# NO2_Output_Processing.net
KiCad netlist of a schematic drawn in Altium Designer
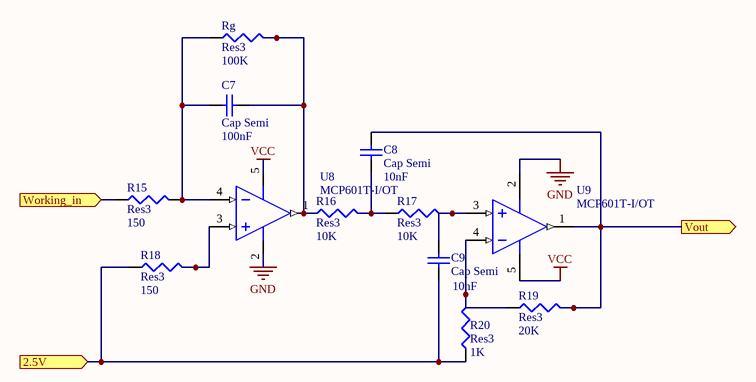
[diagram p0: NO2_Output_Processing.SchDoc]

(export (version "E")
  (design (tool "Eeschema 10.0.6"))
  (components
    (comp (ref "C7")
      (value "Cap Semi")
      (footprint "C1206")
      (description "Capacitor (Semiconductor SIM Model)")
      (fields (field (name "ALTIUM_VALUE") "100nF") (field (name "PUBLISHER") "Altium Limited"))
      (libsource (lib "Miscellaneous Devices") (part "Cap Semi"))
    )
    (comp (ref "C8")
      (value "Cap Semi")
      (footprint "C1206")
      (description "Capacitor (Semiconductor SIM Model)")
      (fields (field (name "ALTIUM_VALUE") "10nF") (field (name "PUBLISHER") "Altium Limited"))
      (libsource (lib "Miscellaneous Devices") (part "Cap Semi"))
    )
    (comp (ref "C9")
      (value "Cap Semi")
      (footprint "C1206")
      (description "Capacitor (Semiconductor SIM Model)")
      (fields (field (name "ALTIUM_VALUE") "10nF") (field (name "PUBLISHER") "Altium Limited"))
      (libsource (lib "Miscellaneous Devices") (part "Cap Semi"))
    )
    (comp (ref "R15")
      (value "Res3")
      (footprint "J1-0603")
      (description "Resistor")
      (fields (field (name "ALTIUM_VALUE") "150") (field (name "PUBLISHER") "Altium Limited"))
      (libsource (lib "Miscellaneous Devices") (part "Res3"))
    )
    (comp (ref "R16")
      (value "Res3")
      (footprint "J1-0603")
      (description "Resistor")
      (fields (field (name "ALTIUM_VALUE") "10K") (field (name "PUBLISHER") "Altium Limited"))
      (libsource (lib "Miscellaneous Devices") (part "Res3"))
    )
    (comp (ref "R17")
      (value "Res3")
      (footprint "J1-0603")
      (description "Resistor")
      (fields (field (name "ALTIUM_VALUE") "10K") (field (name "PUBLISHER") "Altium Limited"))
      (libsource (lib "Miscellaneous Devices") (part "Res3"))
    )
    (comp (ref "R18")
      (value "Res3")
      (footprint "J1-0603")
      (description "Resistor")
      (fields (field (name "ALTIUM_VALUE") "150") (field (name "PUBLISHER") "Altium Limited"))
      (libsource (lib "Miscellaneous Devices") (part "Res3"))
    )
    (comp (ref "R19")
      (value "Res3")
      (footprint "J1-0603")
      (description "Resistor")
      (fields (field (name "ALTIUM_VALUE") "20K") (field (name "PUBLISHER") "Altium Limited"))
      (libsource (lib "Miscellaneous Devices") (part "Res3"))
    )
    (comp (ref "R20")
      (value "Res3")
      (footprint "J1-0603")
      (description "Resistor")
      (fields (field (name "ALTIUM_VALUE") "1K") (field (name "PUBLISHER") "Altium Limited"))
      (libsource (lib "Miscellaneous Devices") (part "Res3"))
    )
    (comp (ref "Rg")
      (value "Res3")
      (footprint "J1-0603")
      (description "Resistor")
      (fields (field (name "ALTIUM_VALUE") "100K") (field (name "PUBLISHER") "Altium Limited"))
      (libsource (lib "Miscellaneous Devices") (part "Res3"))
    )
    (comp (ref "U8")
      (value "MCP601T-I/OT")
      (footprint "SOT-23-OT5_L")
      (libsource (lib "Altium Content Vault") (part "AMP-OPA-MCP601-SOT5"))
    )
    (comp (ref "U9")
      (value "MCP601T-I/OT")
      (footprint "SOT-23-OT5_L")
      (libsource (lib "Altium Content Vault") (part "AMP-OPA-MCP601-SOT5"))
    )
  )
  (nets
    (net (code "1") (name "/2.5V") (class "Default")
      (node (ref "C9") (pin "1") (pinfunction "1_1") (pintype "passive"))
      (node (ref "R18") (pin "1") (pinfunction "1_1") (pintype "passive"))
      (node (ref "R20") (pin "1") (pinfunction "1_1") (pintype "passive"))
    )
    (net (code "2") (name "/Vout") (class "Default")
      (node (ref "C8") (pin "2") (pinfunction "2_2") (pintype "passive"))
      (node (ref "R19") (pin "2") (pinfunction "2_2") (pintype "passive"))
      (node (ref "U9") (pin "1") (pinfunction "VOUT_1") (pintype "output"))
    )
    (net (code "3") (name "/Working_in") (class "Default")
      (node (ref "R15") (pin "1") (pinfunction "1_1") (pintype "passive"))
    )
    (net (code "4") (name "GND") (class "Default")
      (node (ref "U8") (pin "2") (pinfunction "VSS_2") (pintype "power_in"))
      (node (ref "U9") (pin "2") (pinfunction "VSS_2") (pintype "power_in"))
    )
    (net (code "5") (name "Net-(C8-Pad1)") (class "Default")
      (node (ref "C8") (pin "1") (pinfunction "1_1") (pintype "passive"))
      (node (ref "R16") (pin "2") (pinfunction "2_2") (pintype "passive"))
      (node (ref "R17") (pin "1") (pinfunction "1_1") (pintype "passive"))
    )
    (net (code "6") (name "Net-(U8-VIN+)") (class "Default")
      (node (ref "R18") (pin "2") (pinfunction "2_2") (pintype "passive"))
      (node (ref "U8") (pin "3") (pinfunction "VIN+_3") (pintype "input"))
    )
    (net (code "7") (name "Net-(U8-VIN-)") (class "Default")
      (node (ref "C7") (pin "1") (pinfunction "1_1") (pintype "passive"))
      (node (ref "R15") (pin "2") (pinfunction "2_2") (pintype "passive"))
      (node (ref "Rg") (pin "1") (pinfunction "1_1") (pintype "passive"))
      (node (ref "U8") (pin "4") (pinfunction "VIN-_4") (pintype "input"))
    )
    (net (code "8") (name "Net-(U8-VOUT)") (class "Default")
      (node (ref "C7") (pin "2") (pinfunction "2_2") (pintype "passive"))
      (node (ref "R16") (pin "1") (pinfunction "1_1") (pintype "passive"))
      (node (ref "Rg") (pin "2") (pinfunction "2_2") (pintype "passive"))
      (node (ref "U8") (pin "1") (pinfunction "VOUT_1") (pintype "output"))
    )
    (net (code "9") (name "Net-(U9-VIN+)") (class "Default")
      (node (ref "C9") (pin "2") (pinfunction "2_2") (pintype "passive"))
      (node (ref "R17") (pin "2") (pinfunction "2_2") (pintype "passive"))
      (node (ref "U9") (pin "3") (pinfunction "VIN+_3") (pintype "input"))
    )
    (net (code "10") (name "Net-(U9-VIN-)") (class "Default")
      (node (ref "R19") (pin "1") (pinfunction "1_1") (pintype "passive"))
      (node (ref "R20") (pin "2") (pinfunction "2_2") (pintype "passive"))
      (node (ref "U9") (pin "4") (pinfunction "VIN-_4") (pintype "input"))
    )
    (net (code "11") (name "VCC") (class "Default")
      (node (ref "U8") (pin "5") (pinfunction "VDD_5") (pintype "power_in"))
      (node (ref "U9") (pin "5") (pinfunction "VDD_5") (pintype "power_in"))
    )
  )
)
